# LED_high_power.net
KiCad netlist of a schematic drawn in Altium Designer
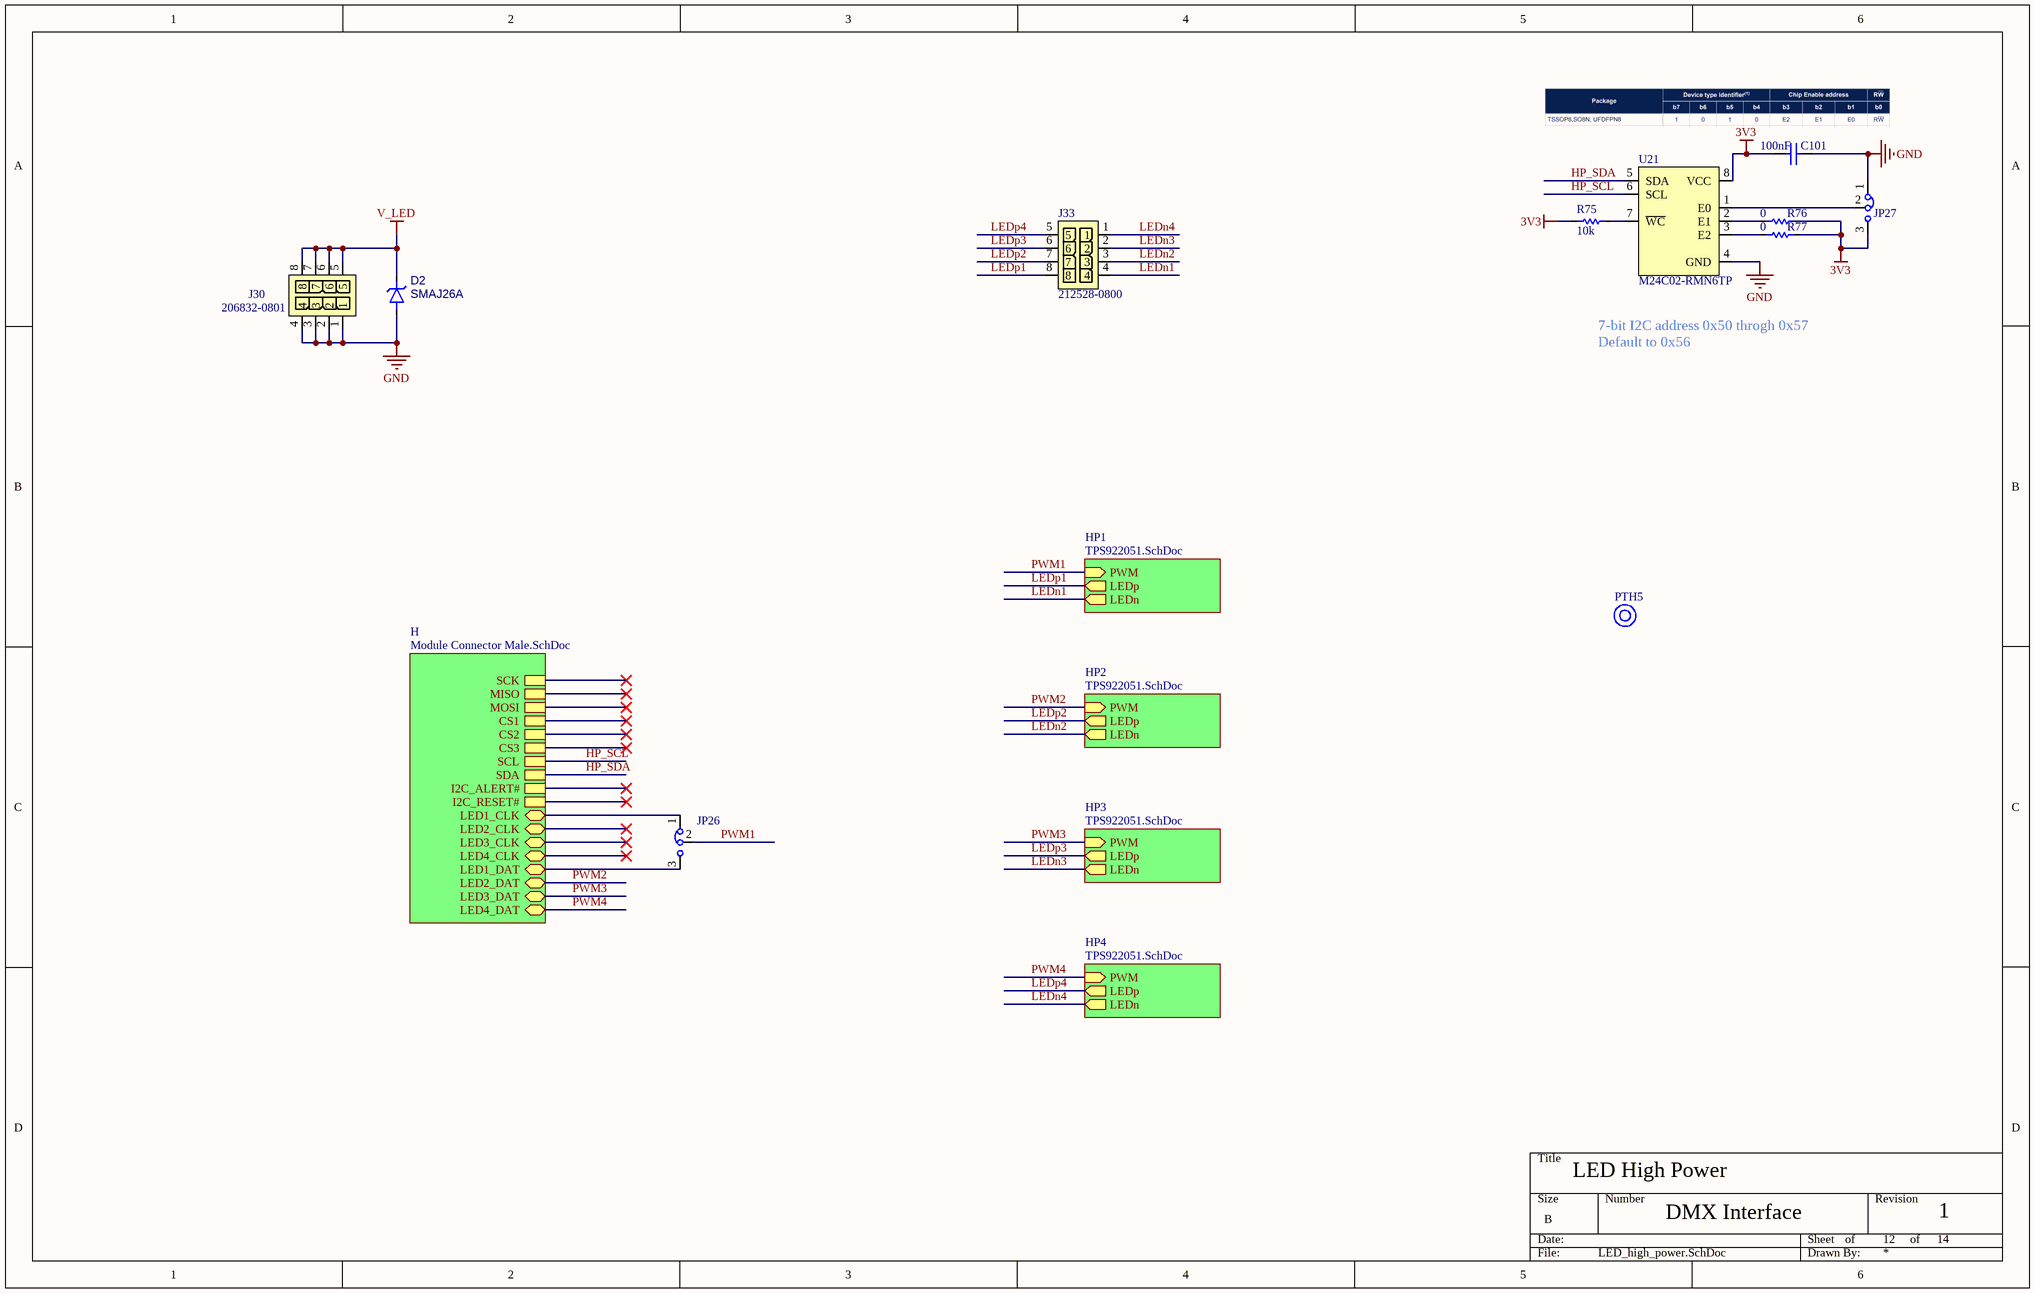
[diagram p0: LED_high_power.SchDoc]

(export (version "E")
  (design (tool "Eeschema 10.0.6"))
  (components
    (comp (ref "C101")
      (value "100nF")
      (footprint "CAPC1608X10N_0603_MED")
      (fields (field (name "Comment") "CC0603KRX7R0BB104"))
      (libsource (lib "Equus Computer Systems") (part "CAP-NP-2"))
    )
    (comp (ref "D2")
      (value "SMAJ26A")
      (footprint "FP-SMAJ-MFG")
      (description "Trans Voltage Suppressor Diode, 400W, 26V V(RWM), Unidirectional, 1 Element, Silicon, DO-214AC")
      (libsource (lib "Equus Computer Systems") (part "DIODE-TVS-2"))
    )
    (comp (ref "J30")
      (value "206832-0801")
      (footprint "206832-0801-Footprint-1")
      (description "Micro-Fit+, Vertical Header, 8 pin")
      (libsource (lib "Equus Computer Systems") (part "206832-0801-Symbol-1"))
    )
    (comp (ref "J33")
      (value "212528-0800")
      (footprint "212528-0800-Footprint")
      (description "Micro-Fit+ RA Header 8 Position")
      (libsource (lib "") (part "206832-0801-Symbol-1_1"))
    )
    (comp (ref "JP26")
      (value "Jumper 3 x 1 Bridge 1-2 Solder Bridge")
      (footprint "Jumper 3 Solder Bridge 1-2 0603")
      (description "0603 Solder Bridge Jumper Surface Mount")
      (fields (field (name "TOLERANCE") "1%"))
      (libsource (lib "Equus Computer Systems") (part "Jumper 3 Bridge 12"))
    )
    (comp (ref "JP27")
      (value "Jumper 3 x 1 Bridge 1-2 Solder Bridge")
      (footprint "Jumper 3 Solder Bridge 1-2 0603")
      (description "0603 Solder Bridge Jumper Surface Mount")
      (fields (field (name "TOLERANCE") "1%"))
      (libsource (lib "") (part "Jumper 3 Bridge 12_1"))
    )
    (comp (ref "PTH5")
      (value "Mounting Hole NPTH")
      (footprint "Mounting Hole M3 No Washer NPTH")
      (libsource (lib "Equus Computer Systems") (part "Mounting Hole NPTH"))
    )
    (comp (ref "R75")
      (value "10k")
      (footprint "RESC1608X06N_0603_MED")
      (fields
        (field (name "TOLERANCE") "1%")
        (field (name "POWER") "100mW")
        (field (name "Comment") "RC0603FR-1010KL")
      )
      (libsource (lib "Equus Computer Systems") (part "RES-2"))
    )
    (comp (ref "R76")
      (value "0")
      (footprint "RESC1608X06N_0603_MED")
      (description "RC Series 0603 0.1 W 0 Ohm Jumper Surface Mount Thick Film Chip Resistor")
      (fields (field (name "POWER") "100mW") (field (name "TOLERANCE") "1%"))
      (libsource (lib "Equus Computer Systems") (part "RES-2"))
    )
    (comp (ref "R77")
      (value "0")
      (footprint "RESC1608X06N_0603_MED")
      (description "RC Series 0603 0.1 W 0 Ohm Jumper Surface Mount Thick Film Chip Resistor")
      (fields (field (name "POWER") "100mW") (field (name "TOLERANCE") "1%"))
      (libsource (lib "Equus Computer Systems") (part "RES-2"))
    )
    (comp (ref "U21")
      (value "M24C02-RMN6TP")
      (footprint "M24C02-RMN6TP-SO8N-IPC_B")
      (description "M24C02 Series 2 Kb (256 x 8) 1.8 V SMT Serial I²C Bus EEPROM - SOIC-8")
      (libsource (lib "Equus Computer Systems") (part "M24C02-RMN6TP"))
    )
  )
  (nets
    (net (code "4") (name "/HP_SCL") (class "Default")
      (node (ref "U21") (pin "6") (pinfunction "SCL_6") (pintype "passive"))
    )
    (net (code "5") (name "/HP_SDA") (class "Default")
      (node (ref "U21") (pin "5") (pinfunction "SDA_5") (pintype "passive"))
    )
    (net (code "8") (name "/LED1_CLK") (class "Default")
      (node (ref "JP26") (pin "1") (pinfunction "1_1") (pintype "passive"))
    )
    (net (code "9") (name "/LED1_DAT") (class "Default")
      (node (ref "JP26") (pin "3") (pinfunction "3_3") (pintype "passive"))
    )
    (net (code "13") (name "/LEDn1") (class "Default")
      (node (ref "J33") (pin "4") (pinfunction "4_4") (pintype "passive"))
    )
    (net (code "14") (name "/LEDn2") (class "Default")
      (node (ref "J33") (pin "3") (pinfunction "3_3") (pintype "passive"))
    )
    (net (code "15") (name "/LEDn3") (class "Default")
      (node (ref "J33") (pin "2") (pinfunction "2_2") (pintype "passive"))
    )
    (net (code "16") (name "/LEDn4") (class "Default")
      (node (ref "J33") (pin "1") (pinfunction "1_1") (pintype "passive"))
    )
    (net (code "17") (name "/LEDp1") (class "Default")
      (node (ref "J33") (pin "8") (pinfunction "8_8") (pintype "passive"))
    )
    (net (code "18") (name "/LEDp2") (class "Default")
      (node (ref "J33") (pin "7") (pinfunction "7_7") (pintype "passive"))
    )
    (net (code "19") (name "/LEDp3") (class "Default")
      (node (ref "J33") (pin "6") (pinfunction "6_6") (pintype "passive"))
    )
    (net (code "20") (name "/LEDp4") (class "Default")
      (node (ref "J33") (pin "5") (pinfunction "5_5") (pintype "passive"))
    )
    (net (code "23") (name "/PWM1") (class "Default")
      (node (ref "JP26") (pin "2") (pinfunction "2_2") (pintype "passive"))
    )
    (net (code "28") (name "3V3") (class "Default")
      (node (ref "C101") (pin "1") (pinfunction "1_1") (pintype "passive"))
      (node (ref "JP27") (pin "3") (pinfunction "3_3") (pintype "passive"))
      (node (ref "R75") (pin "2") (pinfunction "2_2") (pintype "passive"))
      (node (ref "R76") (pin "1") (pinfunction "1_1") (pintype "passive"))
      (node (ref "R77") (pin "1") (pinfunction "1_1") (pintype "passive"))
      (node (ref "U21") (pin "8") (pinfunction "VCC_8") (pintype "power_in"))
    )
    (net (code "29") (name "GND") (class "Default")
      (node (ref "C101") (pin "2") (pinfunction "2_2") (pintype "passive"))
      (node (ref "D2") (pin "2") (pinfunction "A_2") (pintype "passive"))
      (node (ref "J30") (pin "1") (pinfunction "1_1") (pintype "passive"))
      (node (ref "J30") (pin "2") (pinfunction "2_2") (pintype "passive"))
      (node (ref "J30") (pin "3") (pinfunction "3_3") (pintype "passive"))
      (node (ref "J30") (pin "4") (pinfunction "4_4") (pintype "passive"))
      (node (ref "JP27") (pin "1") (pinfunction "1_1") (pintype "passive"))
      (node (ref "U21") (pin "4") (pinfunction "GND_4") (pintype "power_in"))
    )
    (net (code "30") (name "Net-(U21-E0)") (class "Default")
      (node (ref "JP27") (pin "2") (pinfunction "2_2") (pintype "passive"))
      (node (ref "U21") (pin "1") (pinfunction "E0_1") (pintype "passive"))
    )
    (net (code "31") (name "Net-(U21-E1)") (class "Default")
      (node (ref "R76") (pin "2") (pinfunction "2_2") (pintype "passive"))
      (node (ref "U21") (pin "2") (pinfunction "E1_2") (pintype "passive"))
    )
    (net (code "32") (name "Net-(U21-E2)") (class "Default")
      (node (ref "R77") (pin "2") (pinfunction "2_2") (pintype "passive"))
      (node (ref "U21") (pin "3") (pinfunction "E2_3") (pintype "passive"))
    )
    (net (code "33") (name "Net-(U21-~{WC})") (class "Default")
      (node (ref "R75") (pin "1") (pinfunction "1_1") (pintype "passive"))
      (node (ref "U21") (pin "7") (pinfunction "~{WC}_7") (pintype "passive"))
    )
    (net (code "34") (name "V_LED") (class "Default")
      (node (ref "D2") (pin "1") (pinfunction "K_1") (pintype "passive"))
      (node (ref "J30") (pin "5") (pinfunction "5_5") (pintype "passive"))
      (node (ref "J30") (pin "6") (pinfunction "6_6") (pintype "passive"))
      (node (ref "J30") (pin "7") (pinfunction "7_7") (pintype "passive"))
      (node (ref "J30") (pin "8") (pinfunction "8_8") (pintype "passive"))
    )
  )
)
